# Logic.net
KiCad netlist of a schematic drawn in EAGLE
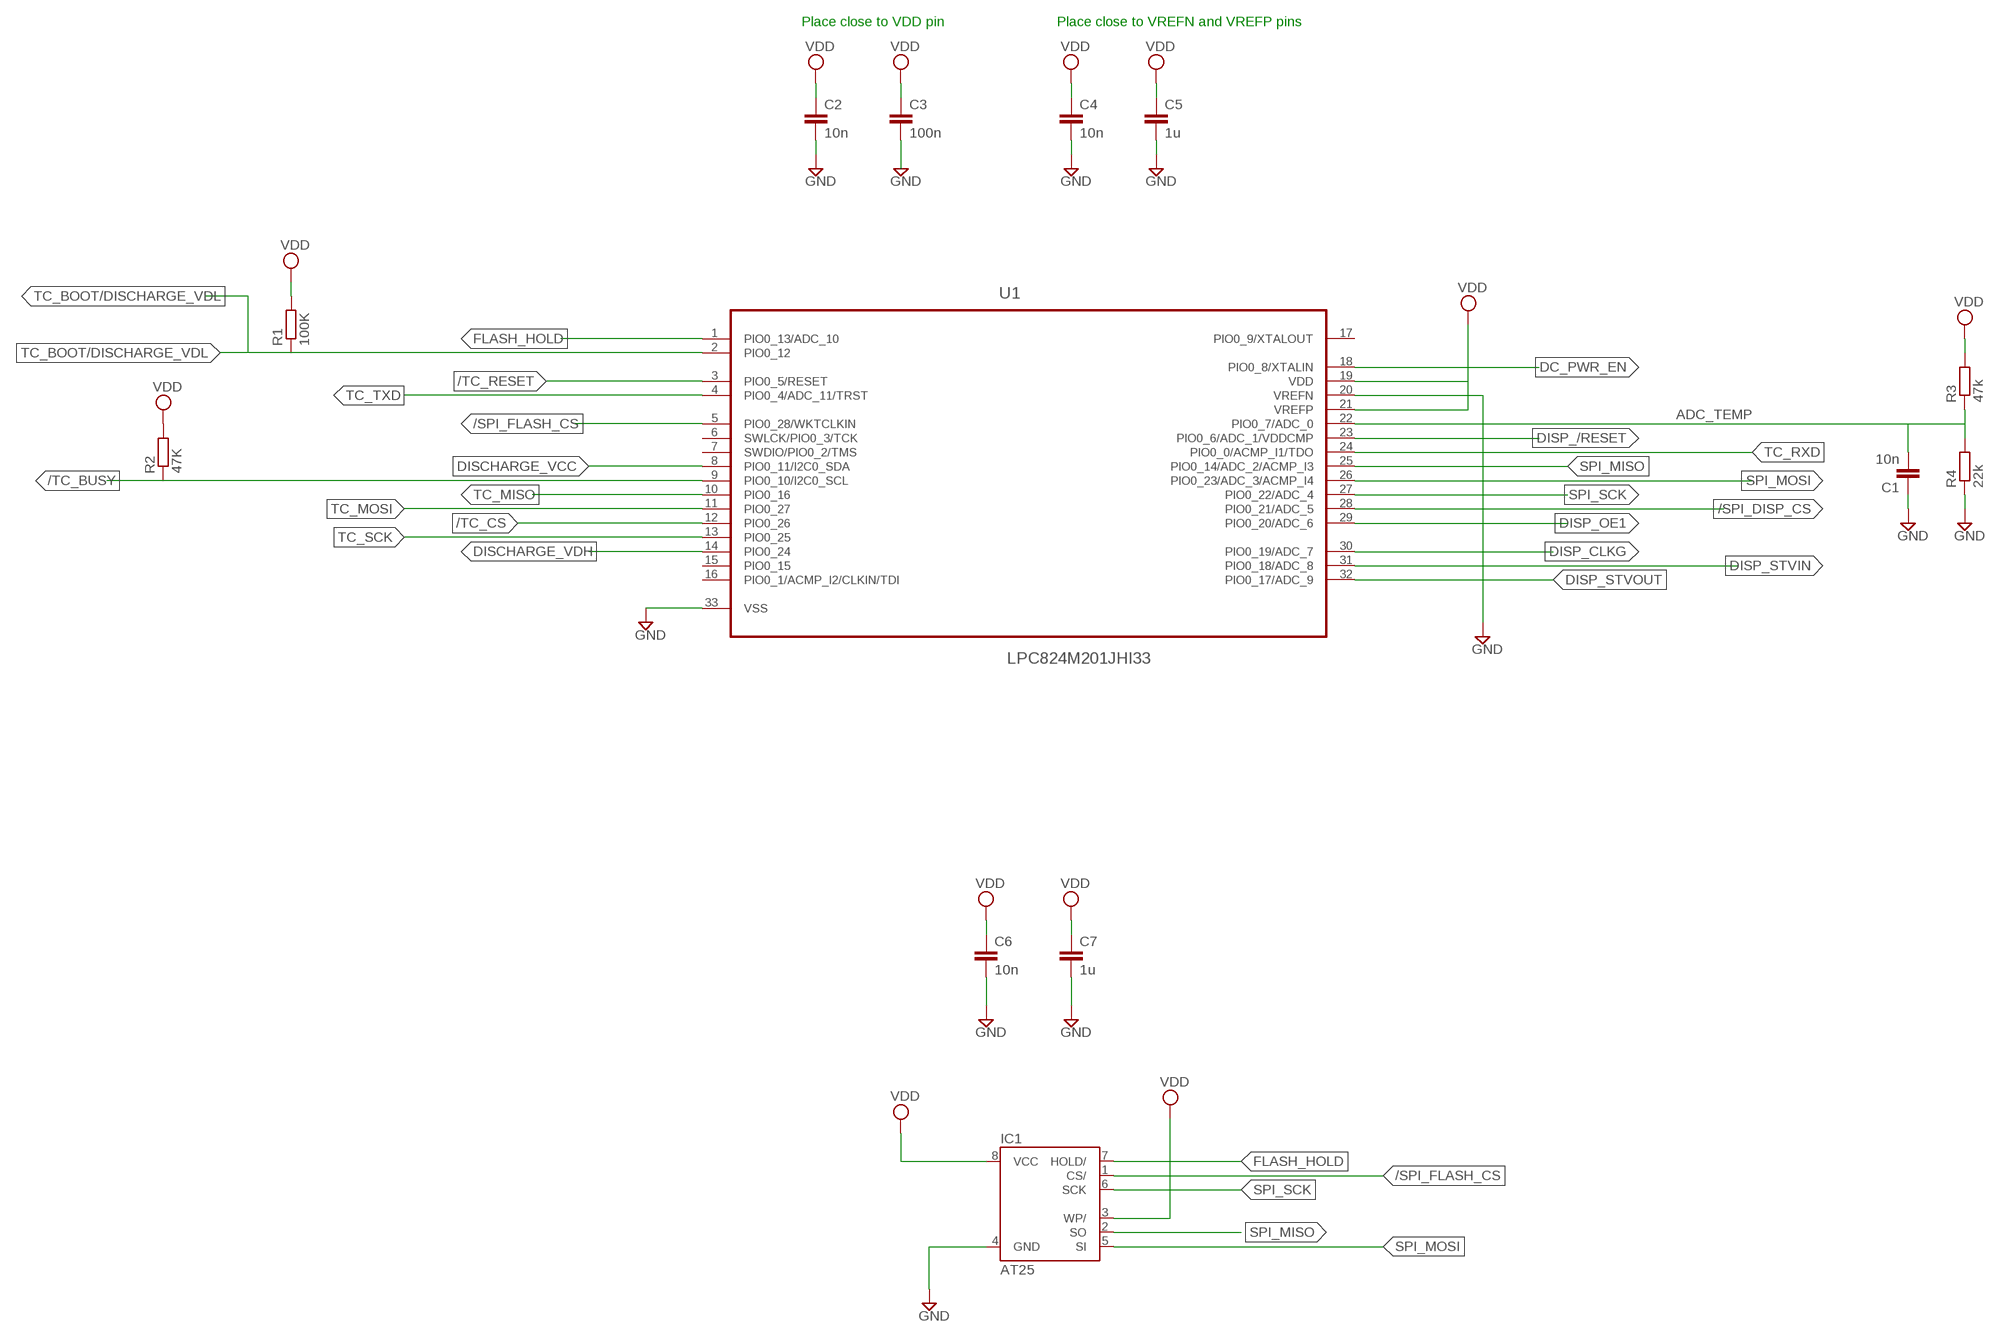
[diagram p0: schematic, sheet 1]

(export (version "E")
  (design (tool "Eeschema 10.0.6"))
  (components
    (comp (ref "C1")
      (value "10n")
      (footprint "eagle-import:C0603")
      (libsource (lib "eagle-import") (part "resistor_C-EUC0603"))
    )
    (comp (ref "C2")
      (value "10n")
      (footprint "eagle-import:C0603")
      (libsource (lib "eagle-import") (part "C-EUC0603"))
    )
    (comp (ref "C3")
      (value "100n")
      (footprint "eagle-import:C0603")
      (libsource (lib "eagle-import") (part "C-EUC0603"))
    )
    (comp (ref "C4")
      (value "10n")
      (footprint "eagle-import:C0603")
      (libsource (lib "eagle-import") (part "C-EUC0603"))
    )
    (comp (ref "C5")
      (value "1u")
      (footprint "eagle-import:C0603")
      (libsource (lib "eagle-import") (part "C-EUC0603"))
    )
    (comp (ref "C6")
      (value "10n")
      (footprint "eagle-import:C0603")
      (libsource (lib "eagle-import") (part "C-EUC0603"))
    )
    (comp (ref "C7")
      (value "1u")
      (footprint "eagle-import:C0603")
      (libsource (lib "eagle-import") (part "C-EUC0603"))
    )
    (comp (ref "IC1")
      (value "AT25")
      (footprint "eagle-import:SOIC8")
      (libsource (lib "eagle-import") (part "AT25"))
    )
    (comp (ref "R1")
      (value "100K")
      (footprint "eagle-import:R0603")
      (libsource (lib "eagle-import") (part "resistor_R-EU_R0603"))
    )
    (comp (ref "R2")
      (value "47K")
      (footprint "eagle-import:R0603")
      (libsource (lib "eagle-import") (part "R-EU_R0603"))
    )
    (comp (ref "R3")
      (value "47k")
      (footprint "eagle-import:R0603")
      (libsource (lib "eagle-import") (part "resistor_R-EU_R0603"))
    )
    (comp (ref "R4")
      (value "22k")
      (footprint "eagle-import:R0603")
      (libsource (lib "eagle-import") (part "resistor_R-EU_R0603"))
    )
    (comp (ref "U1")
      (value "LPC824M201JHI33")
      (footprint "eagle-import:QFN65P700X700X100-33N")
      (fields (field (name "MPN") "LPC1114FHN33/201,5"))
      (libsource (lib "eagle-import") (part "LPC824M201JHI33"))
    )
  )
  (nets
    (net (code "1") (name "/ADC_TEMP") (class "Default")
      (node (ref "C1") (pin "2") (pinfunction "2_2") (pintype "passive"))
      (node (ref "R3") (pin "1") (pinfunction "1_1") (pintype "passive"))
      (node (ref "R4") (pin "2") (pinfunction "2_2") (pintype "passive"))
      (node (ref "U1") (pin "22") (pinfunction "PIO0_7/ADC_0_22") (pintype "bidirectional"))
    )
    (net (code "2") (name "DC_PWR_EN") (class "Default")
      (node (ref "U1") (pin "18") (pinfunction "PIO0_8/XTALIN_18") (pintype "bidirectional"))
    )
    (net (code "3") (name "DISCHARGE_VCC") (class "Default")
      (node (ref "U1") (pin "8") (pinfunction "PIO0_11/I2C0_SDA_8") (pintype "bidirectional"))
    )
    (net (code "4") (name "DISCHARGE_VDH") (class "Default")
      (node (ref "U1") (pin "14") (pinfunction "PIO0_24_14") (pintype "bidirectional"))
    )
    (net (code "5") (name "DISP_CLKG") (class "Default")
      (node (ref "U1") (pin "30") (pinfunction "PIO0_19/ADC_7_30") (pintype "bidirectional"))
    )
    (net (code "6") (name "DISP_OE1") (class "Default")
      (node (ref "U1") (pin "29") (pinfunction "PIO0_20/ADC_6_29") (pintype "bidirectional"))
    )
    (net (code "7") (name "DISP_STVIN") (class "Default")
      (node (ref "U1") (pin "31") (pinfunction "PIO0_18/ADC_8_31") (pintype "bidirectional"))
    )
    (net (code "8") (name "DISP_STVOUT") (class "Default")
      (node (ref "U1") (pin "32") (pinfunction "PIO0_17/ADC_9_32") (pintype "bidirectional"))
    )
    (net (code "9") (name "DISP_{slash}RESET") (class "Default")
      (node (ref "U1") (pin "23") (pinfunction "PIO0_6/ADC_1/VDDCMP_23") (pintype "bidirectional"))
    )
    (net (code "10") (name "FLASH_HOLD") (class "Default")
      (node (ref "IC1") (pin "7") (pinfunction "HOLD/_7") (pintype "input"))
      (node (ref "U1") (pin "1") (pinfunction "PIO0_13/ADC_10_1") (pintype "bidirectional"))
    )
    (net (code "11") (name "GND") (class "Default")
      (node (ref "C1") (pin "1") (pinfunction "1_1") (pintype "passive"))
      (node (ref "C2") (pin "2") (pinfunction "2_2") (pintype "passive"))
      (node (ref "C4") (pin "2") (pinfunction "2_2") (pintype "passive"))
      (node (ref "C5") (pin "2") (pinfunction "2_2") (pintype "passive"))
      (node (ref "C6") (pin "2") (pinfunction "2_2") (pintype "passive"))
      (node (ref "C7") (pin "2") (pinfunction "2_2") (pintype "passive"))
      (node (ref "IC1") (pin "4") (pinfunction "GND_4") (pintype "power_in"))
      (node (ref "R4") (pin "1") (pinfunction "1_1") (pintype "passive"))
      (node (ref "U1") (pin "20") (pinfunction "VREFN_20") (pintype "power_in"))
      (node (ref "U1") (pin "33") (pinfunction "VSS_33") (pintype "passive"))
    )
    (net (code "12") (name "SPI_MISO") (class "Default")
      (node (ref "IC1") (pin "2") (pinfunction "SO_2") (pintype "input"))
      (node (ref "U1") (pin "25") (pinfunction "PIO0_14/ADC_2/ACMP_I3_25") (pintype "bidirectional"))
    )
    (net (code "13") (name "SPI_MOSI") (class "Default")
      (node (ref "IC1") (pin "5") (pinfunction "SI_5") (pintype "bidirectional"))
      (node (ref "U1") (pin "26") (pinfunction "PIO0_23/ADC_3/ACMP_I4_26") (pintype "bidirectional"))
    )
    (net (code "14") (name "SPI_SCK") (class "Default")
      (node (ref "IC1") (pin "6") (pinfunction "SCK_6") (pintype "bidirectional"))
      (node (ref "U1") (pin "27") (pinfunction "PIO0_22/ADC_4_27") (pintype "bidirectional"))
    )
    (net (code "15") (name "TC_BOOT{slash}DISCHARGE_VDL") (class "Default")
      (node (ref "R1") (pin "1") (pinfunction "1_1") (pintype "passive"))
      (node (ref "U1") (pin "2") (pinfunction "PIO0_12_2") (pintype "bidirectional"))
    )
    (net (code "16") (name "TC_MISO") (class "Default")
      (node (ref "U1") (pin "10") (pinfunction "PIO0_16_10") (pintype "bidirectional"))
    )
    (net (code "17") (name "TC_MOSI") (class "Default")
      (node (ref "U1") (pin "11") (pinfunction "PIO0_27_11") (pintype "bidirectional"))
    )
    (net (code "18") (name "TC_RXD") (class "Default")
      (node (ref "U1") (pin "24") (pinfunction "PIO0_0/ACMP_I1/TDO_24") (pintype "bidirectional"))
    )
    (net (code "19") (name "TC_SCK") (class "Default")
      (node (ref "U1") (pin "13") (pinfunction "PIO0_25_13") (pintype "bidirectional"))
    )
    (net (code "20") (name "TC_TXD") (class "Default")
      (node (ref "U1") (pin "4") (pinfunction "PIO0_4/ADC_11/TRST_4") (pintype "bidirectional"))
    )
    (net (code "21") (name "VDD") (class "Default")
      (node (ref "C2") (pin "1") (pinfunction "1_1") (pintype "passive"))
      (node (ref "C3") (pin "1") (pinfunction "1_1") (pintype "passive"))
      (node (ref "C4") (pin "1") (pinfunction "1_1") (pintype "passive"))
      (node (ref "C5") (pin "1") (pinfunction "1_1") (pintype "passive"))
      (node (ref "C6") (pin "1") (pinfunction "1_1") (pintype "passive"))
      (node (ref "C7") (pin "1") (pinfunction "1_1") (pintype "passive"))
      (node (ref "IC1") (pin "3") (pinfunction "WP/_3") (pintype "input"))
      (node (ref "IC1") (pin "8") (pinfunction "VCC_8") (pintype "power_in"))
      (node (ref "R1") (pin "2") (pinfunction "2_2") (pintype "passive"))
      (node (ref "R2") (pin "2") (pinfunction "2_2") (pintype "passive"))
      (node (ref "R3") (pin "2") (pinfunction "2_2") (pintype "passive"))
      (node (ref "U1") (pin "19") (pinfunction "VDD_19") (pintype "power_in"))
      (node (ref "U1") (pin "21") (pinfunction "VREFP_21") (pintype "power_in"))
    )
    (net (code "22") (name "unconnected-(C3-Pad2)") (class "Default")
      (node (ref "C3") (pin "2") (pinfunction "2_2") (pintype "passive"))
    )
    (net (code "23") (name "unconnected-(U1-PIO0_1{slash}ACMP_I2{slash}CLKIN{slash}TDI-Pad16)") (class "Default")
      (node (ref "U1") (pin "16") (pinfunction "PIO0_1/ACMP_I2/CLKIN/TDI_16") (pintype "no_connect"))
    )
    (net (code "24") (name "unconnected-(U1-PIO0_9{slash}XTALOUT-Pad17)") (class "Default")
      (node (ref "U1") (pin "17") (pinfunction "PIO0_9/XTALOUT_17") (pintype "no_connect"))
    )
    (net (code "25") (name "unconnected-(U1-PIO0_15-Pad15)") (class "Default")
      (node (ref "U1") (pin "15") (pinfunction "PIO0_15_15") (pintype "no_connect"))
    )
    (net (code "26") (name "unconnected-(U1-SWDIO{slash}PIO0_2{slash}TMS-Pad7)") (class "Default")
      (node (ref "U1") (pin "7") (pinfunction "SWDIO/PIO0_2/TMS_7") (pintype "no_connect"))
    )
    (net (code "27") (name "unconnected-(U1-SWLCK{slash}PIO0_3{slash}TCK-Pad6)") (class "Default")
      (node (ref "U1") (pin "6") (pinfunction "SWLCK/PIO0_3/TCK_6") (pintype "no_connect"))
    )
    (net (code "28") (name "{slash}SPI_DISP_CS") (class "Default")
      (node (ref "U1") (pin "28") (pinfunction "PIO0_21/ADC_5_28") (pintype "bidirectional"))
    )
    (net (code "29") (name "{slash}SPI_FLASH_CS") (class "Default")
      (node (ref "IC1") (pin "1") (pinfunction "CS/_1") (pintype "input"))
      (node (ref "U1") (pin "5") (pinfunction "PIO0_28/WKTCLKIN_5") (pintype "bidirectional"))
    )
    (net (code "30") (name "{slash}TC_BUSY") (class "Default")
      (node (ref "R2") (pin "1") (pinfunction "1_1") (pintype "passive"))
      (node (ref "U1") (pin "9") (pinfunction "PIO0_10/I2C0_SCL_9") (pintype "bidirectional"))
    )
    (net (code "31") (name "{slash}TC_CS") (class "Default")
      (node (ref "U1") (pin "12") (pinfunction "PIO0_26_12") (pintype "bidirectional"))
    )
    (net (code "32") (name "{slash}TC_RESET") (class "Default")
      (node (ref "U1") (pin "3") (pinfunction "PIO0_5/RESET_3") (pintype "bidirectional"))
    )
  )
)
